# id_eeprom.net
KiCad netlist of a schematic drawn in Altium Designer
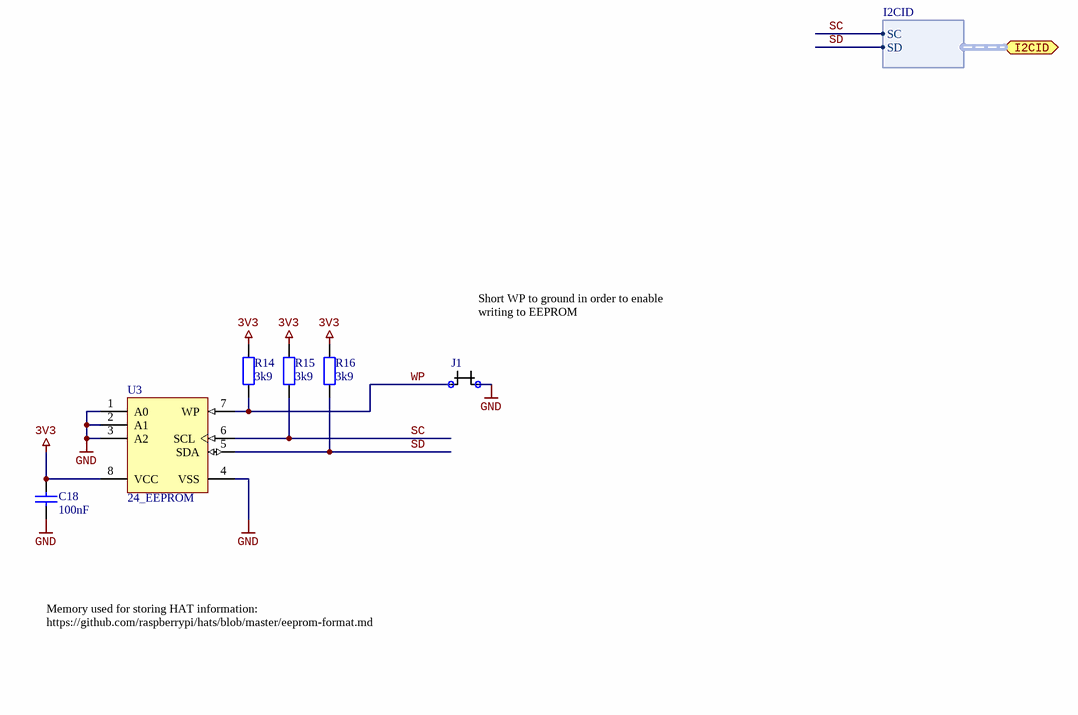
[diagram p0: id_eeprom.SchDoc]

(export (version "E")
  (design (tool "Eeschema 10.0.6"))
  (components
    (comp (ref "C18")
      (value "100nF")
      (footprint "CAPC1608N")
      (description "Capacitor")
      (libsource (lib "Discrete") (part "Capacitor"))
    )
    (comp (ref "J1")
      (value "Jumper")
      (footprint "JUMPER")
      (libsource (lib "my_various_devices") (part "Jumper"))
    )
    (comp (ref "R14")
      (value "3k9")
      (footprint "Chip_Resistor_N:RESC1608N")
      (description "Resistor")
      (fields (field (name "TOLERANCE") "5%") (field (name "POWER") "0W"))
      (libsource (lib "Discrete") (part "Resistor"))
    )
    (comp (ref "R15")
      (value "3k9")
      (footprint "Chip_Resistor_N:RESC1608N")
      (description "Resistor")
      (fields (field (name "TOLERANCE") "5%") (field (name "POWER") "0W"))
      (libsource (lib "Discrete") (part "Resistor"))
    )
    (comp (ref "R16")
      (value "3k9")
      (footprint "Chip_Resistor_N:RESC1608N")
      (description "Resistor")
      (fields (field (name "TOLERANCE") "5%") (field (name "POWER") "0W"))
      (libsource (lib "Discrete") (part "Resistor"))
    )
    (comp (ref "U3")
      (value "24_EEPROM")
      (footprint "SO-8_L")
      (description "16Kbit, 400kHz, 2.5V, I2C Serial EEPROM, 8-Pin SOIC 150mil, Extended Temperature")
      (libsource (lib "my_various_devices") (part "24_EEPROM"))
    )
  )
  (nets
    (net (code "2") (name "/SC") (class "Default")
      (node (ref "R15") (pin "2") (pinfunction "2_2") (pintype "passive"))
      (node (ref "U3") (pin "6") (pinfunction "SCL_6") (pintype "input"))
    )
    (net (code "3") (name "/SD") (class "Default")
      (node (ref "R16") (pin "2") (pinfunction "2_2") (pintype "passive"))
      (node (ref "U3") (pin "5") (pinfunction "SDA_5") (pintype "bidirectional"))
    )
    (net (code "4") (name "/WP") (class "Default")
      (node (ref "J1") (pin "1") (pinfunction "1_1") (pintype "passive"))
      (node (ref "R14") (pin "2") (pinfunction "2_2") (pintype "passive"))
      (node (ref "U3") (pin "7") (pinfunction "WP_7") (pintype "input"))
    )
    (net (code "6") (name "3V3") (class "Default")
      (node (ref "C18") (pin "2") (pinfunction "2_2") (pintype "passive"))
      (node (ref "R14") (pin "1") (pinfunction "1_1") (pintype "passive"))
      (node (ref "R15") (pin "1") (pinfunction "1_1") (pintype "passive"))
      (node (ref "R16") (pin "1") (pinfunction "1_1") (pintype "passive"))
      (node (ref "U3") (pin "8") (pinfunction "VCC_8") (pintype "power_in"))
    )
    (net (code "7") (name "GND") (class "Default")
      (node (ref "C18") (pin "1") (pinfunction "1_1") (pintype "passive"))
      (node (ref "J1") (pin "2") (pinfunction "2_2") (pintype "passive"))
      (node (ref "U3") (pin "1") (pinfunction "A0_1") (pintype "passive"))
      (node (ref "U3") (pin "2") (pinfunction "A1_2") (pintype "passive"))
      (node (ref "U3") (pin "3") (pinfunction "A2_3") (pintype "passive"))
      (node (ref "U3") (pin "4") (pinfunction "VSS_4") (pintype "power_in"))
    )
  )
)
